# CAN_Tranceiver.net
KiCad netlist of a schematic drawn in Altium Designer
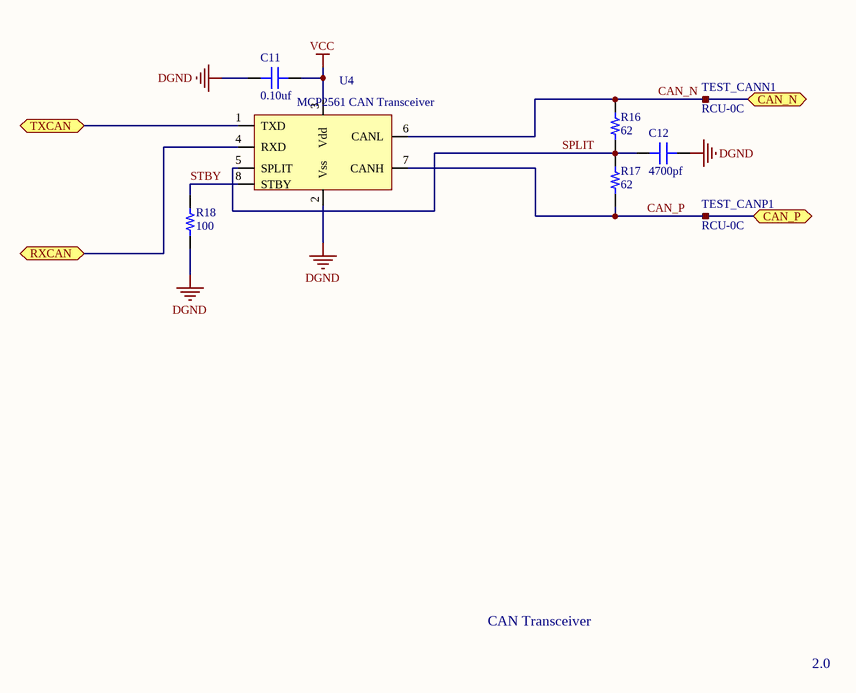
[diagram p0: CAN_Tranceiver.SchDoc]

(export (version "E")
  (design (tool "Eeschema 10.0.6"))
  (components
    (comp (ref "C11")
      (value "0.10uf")
      (footprint "CAP 0603/1608")
      (fields
        (field (name "Comment") "Capacitor MLCC 0.10uf 50V CAP 0603/1608")
        (field (name "CREATED_BY") "Nick Mah")
      )
      (libsource (lib "Altium-Lib") (part "Capacitor"))
    )
    (comp (ref "C12")
      (value "4700pf")
      (footprint "CAP 0603/1608")
      (fields
        (field (name "Comment") "Capacitor MLCC 4700pf 50V CAP 0603/1608")
        (field (name "CREATED_BY") "Nick Mah")
      )
      (libsource (lib "Altium-Lib") (part "Capacitor"))
    )
    (comp (ref "R16")
      (value "62")
      (footprint "RES 0603/1608")
      (fields
        (field (name "TOLERANCE") "5%")
        (field (name "POWER") "1/10W")
        (field (name "Comment") "Resistor 62 0603 1/10W 5%")
        (field (name "CREATED_BY") "Nick Mah")
      )
      (libsource (lib "Altium-Lib") (part "Resistor"))
    )
    (comp (ref "R17")
      (value "62")
      (footprint "RES 0603/1608")
      (fields
        (field (name "TOLERANCE") "5%")
        (field (name "POWER") "1/10W")
        (field (name "Comment") "Resistor 62 0603 1/10W 5%")
        (field (name "CREATED_BY") "Nick Mah")
      )
      (libsource (lib "Altium-Lib") (part "Resistor"))
    )
    (comp (ref "R18")
      (value "100")
      (footprint "RES 0603/1608")
      (fields
        (field (name "TOLERANCE") "10%")
        (field (name "POWER") "1/10W")
        (field (name "Comment") "Resistor 100 0603 1/10W 10%")
        (field (name "CREATED_BY") "Nick Mah")
      )
      (libsource (lib "Altium-Lib") (part "Resistor"))
    )
    (comp (ref "TEST_CANN1")
      (value "RCU-0C")
      (footprint "RCU-0C")
      (libsource (lib "Altium-Lib") (part "RCU-0C"))
    )
    (comp (ref "TEST_CANP1")
      (value "RCU-0C")
      (footprint "RCU-0C")
      (libsource (lib "Altium-Lib") (part "RCU-0C"))
    )
    (comp (ref "U4")
      (value "MCP2561 CAN Transceiver")
      (footprint "SOIC-8")
      (fields (field (name "MFRPARTNO") "MCP2561") (field (name "CREATED_BY") "Angel Delgado"))
      (libsource (lib "Altium-Lib") (part "MCP2561 CAN Transceiver"))
    )
  )
  (nets
    (net (code "1") (name "/CAN_N") (class "Default")
      (node (ref "R16") (pin "1") (pinfunction "1_1") (pintype "passive"))
      (node (ref "TEST_CANN1") (pin "1") (pintype "passive"))
      (node (ref "U4") (pin "6") (pinfunction "CANL_6") (pintype "passive"))
    )
    (net (code "2") (name "/CAN_P") (class "Default")
      (node (ref "R17") (pin "2") (pinfunction "2_2") (pintype "passive"))
      (node (ref "TEST_CANP1") (pin "1") (pintype "passive"))
      (node (ref "U4") (pin "7") (pinfunction "CANH_7") (pintype "passive"))
    )
    (net (code "3") (name "/RXCAN") (class "Default")
      (node (ref "U4") (pin "4") (pinfunction "RXD_4") (pintype "passive"))
    )
    (net (code "4") (name "/SPLIT") (class "Default")
      (node (ref "C12") (pin "2") (pinfunction "2_2") (pintype "passive"))
      (node (ref "R16") (pin "2") (pinfunction "2_2") (pintype "passive"))
      (node (ref "R17") (pin "1") (pinfunction "1_1") (pintype "passive"))
      (node (ref "U4") (pin "5") (pinfunction "SPLIT_5") (pintype "passive"))
    )
    (net (code "5") (name "/STBY") (class "Default")
      (node (ref "R18") (pin "2") (pinfunction "2_2") (pintype "passive"))
      (node (ref "U4") (pin "8") (pinfunction "STBY_8") (pintype "passive"))
    )
    (net (code "6") (name "/TXCAN") (class "Default")
      (node (ref "U4") (pin "1") (pinfunction "TXD_1") (pintype "passive"))
    )
    (net (code "7") (name "DGND") (class "Default")
      (node (ref "C11") (pin "1") (pinfunction "1_1") (pintype "passive"))
      (node (ref "C12") (pin "1") (pinfunction "1_1") (pintype "passive"))
      (node (ref "R18") (pin "1") (pinfunction "1_1") (pintype "passive"))
      (node (ref "U4") (pin "2") (pinfunction "Vss_2") (pintype "passive"))
    )
    (net (code "8") (name "VCC") (class "Default")
      (node (ref "C11") (pin "2") (pinfunction "2_2") (pintype "passive"))
      (node (ref "U4") (pin "3") (pinfunction "Vdd_3") (pintype "passive"))
    )
  )
)
